# Siren_Buzzer_Mounting_Schematic.net
KiCad netlist of a schematic drawn in Altium Designer
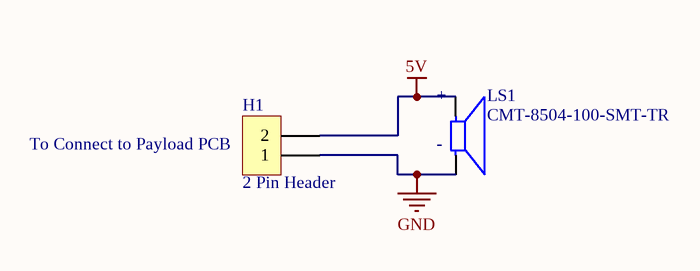
[diagram p0: Siren_Buzzer Mounting Schematic.SchDoc]

(export (version "E")
  (design (tool "Eeschema 10.0.6"))
  (components
    (comp (ref "H1")
      (value "2 Pin Header")
      (footprint "2 Pin Header")
      (libsource (lib "Different Header Pin Numbers") (part "2 Pin Header"))
    )
    (comp (ref "LS1")
      (value "CMT-8504-100-SMT-TR")
      (footprint "XDCR_CMT-8504-100-SMT-TR")
      (description "8.5 mm, 5 Vo-p, 100 dB, Surface Mount (SMT), Magnetic Audio Transducer Buzzer")
      (fields (field (name "MF") "CUI Devices"))
      (libsource (lib "CMT-8504-100-SMT-TR") (part "CMT-8504-100-SMT-TR"))
    )
  )
  (nets
    (net (code "1") (name "5V") (class "Default")
      (node (ref "H1") (pin "2") (pinfunction "2_2") (pintype "passive"))
      (node (ref "LS1") (pin "P") (pinfunction "P_P") (pintype "passive"))
    )
    (net (code "2") (name "GND") (class "Default")
      (node (ref "H1") (pin "1") (pinfunction "1_1") (pintype "passive"))
      (node (ref "LS1") (pin "N") (pinfunction "N_N") (pintype "passive"))
    )
  )
)
